# X16-Backplane1.net
KiCad netlist of a schematic drawn in EAGLE
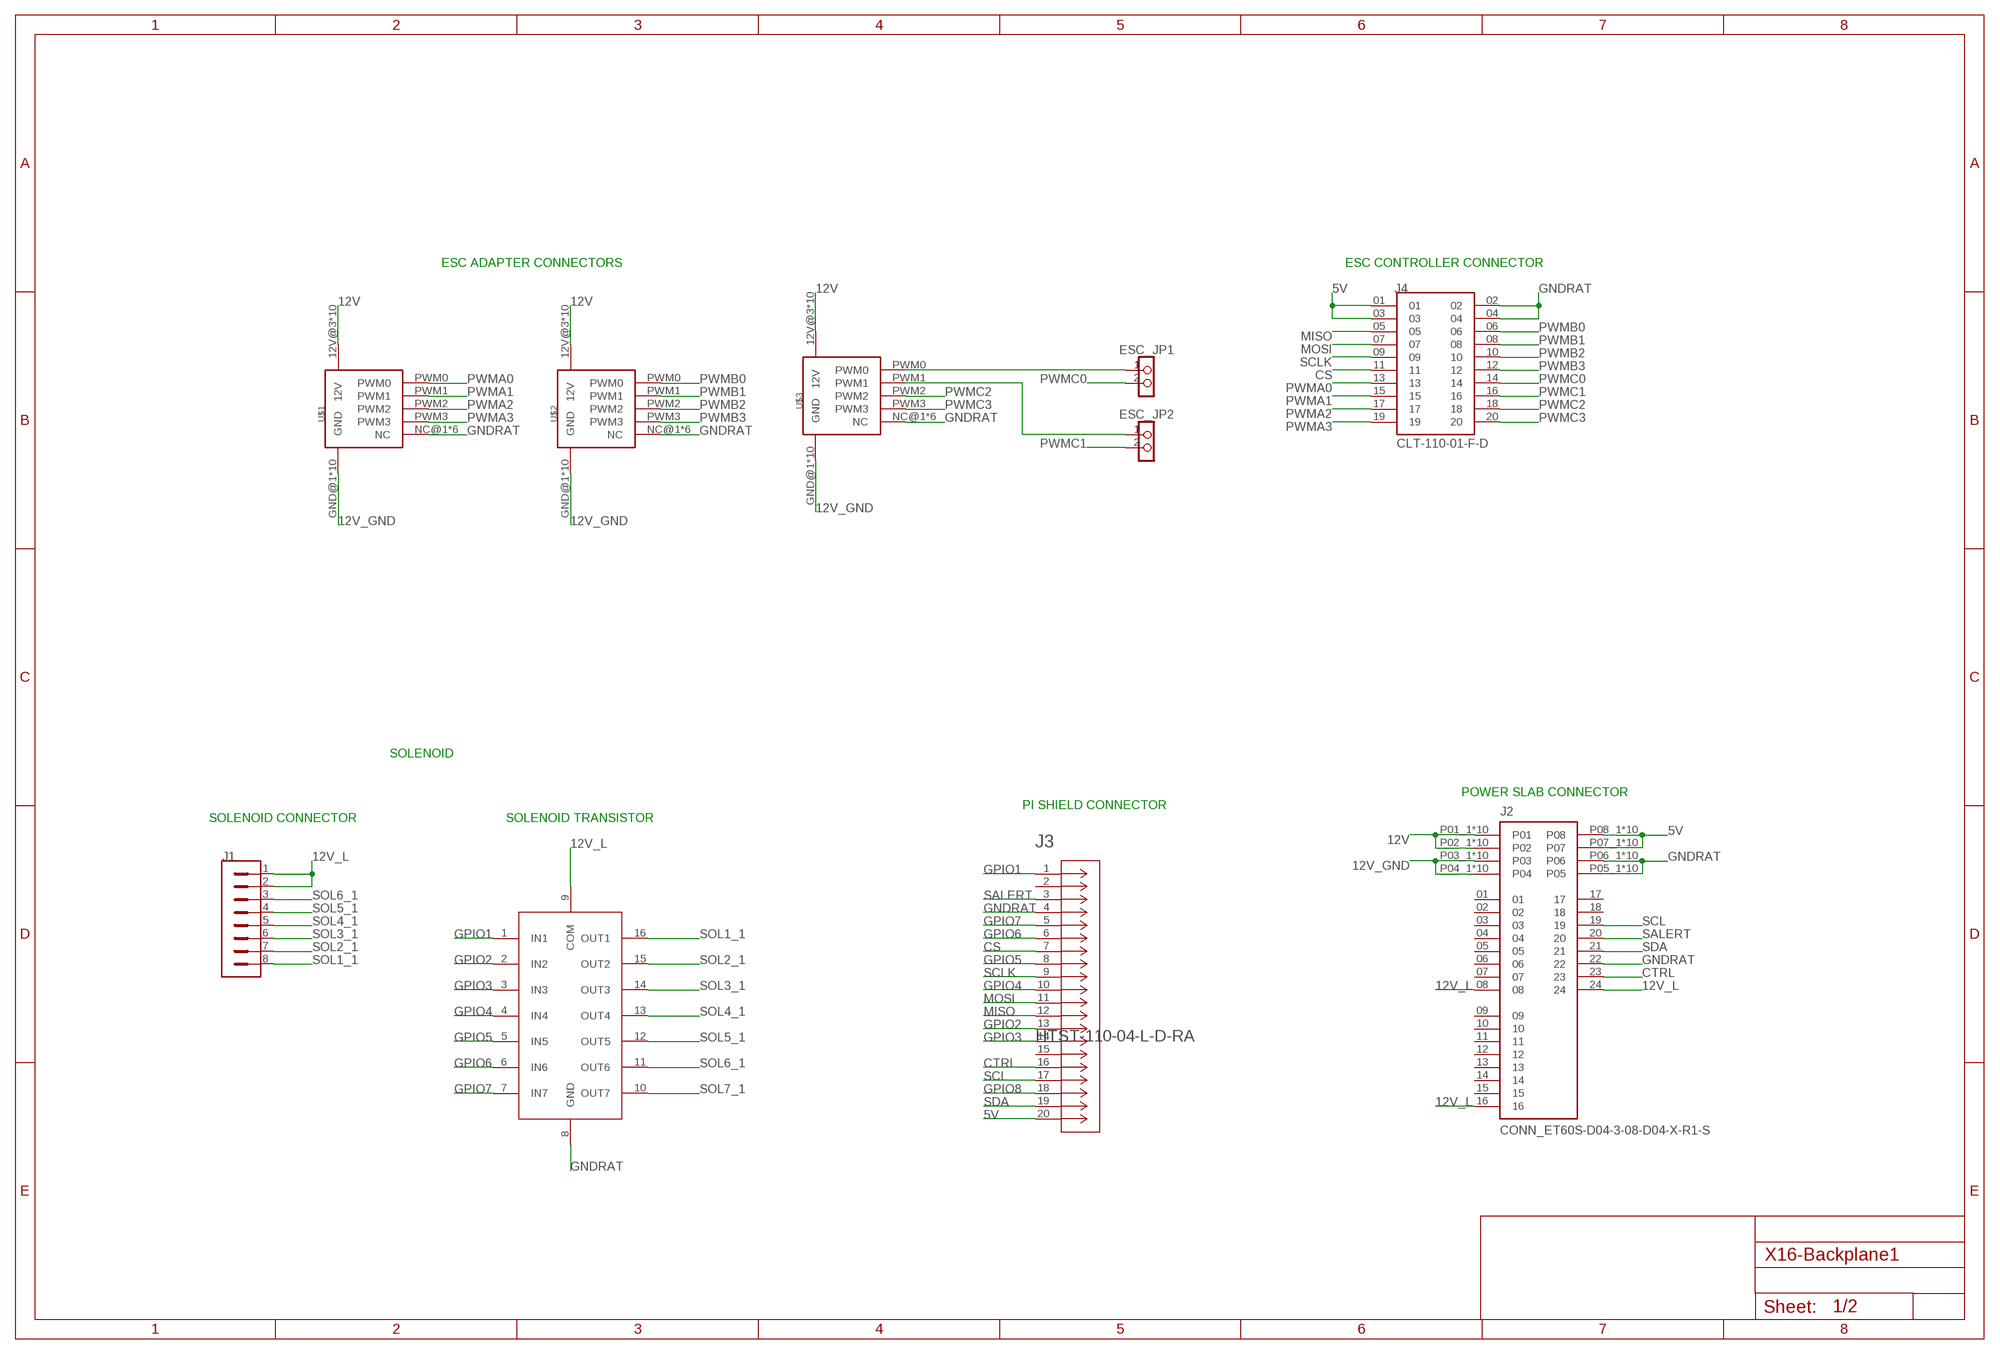
[diagram p0: schematic, sheet 1]
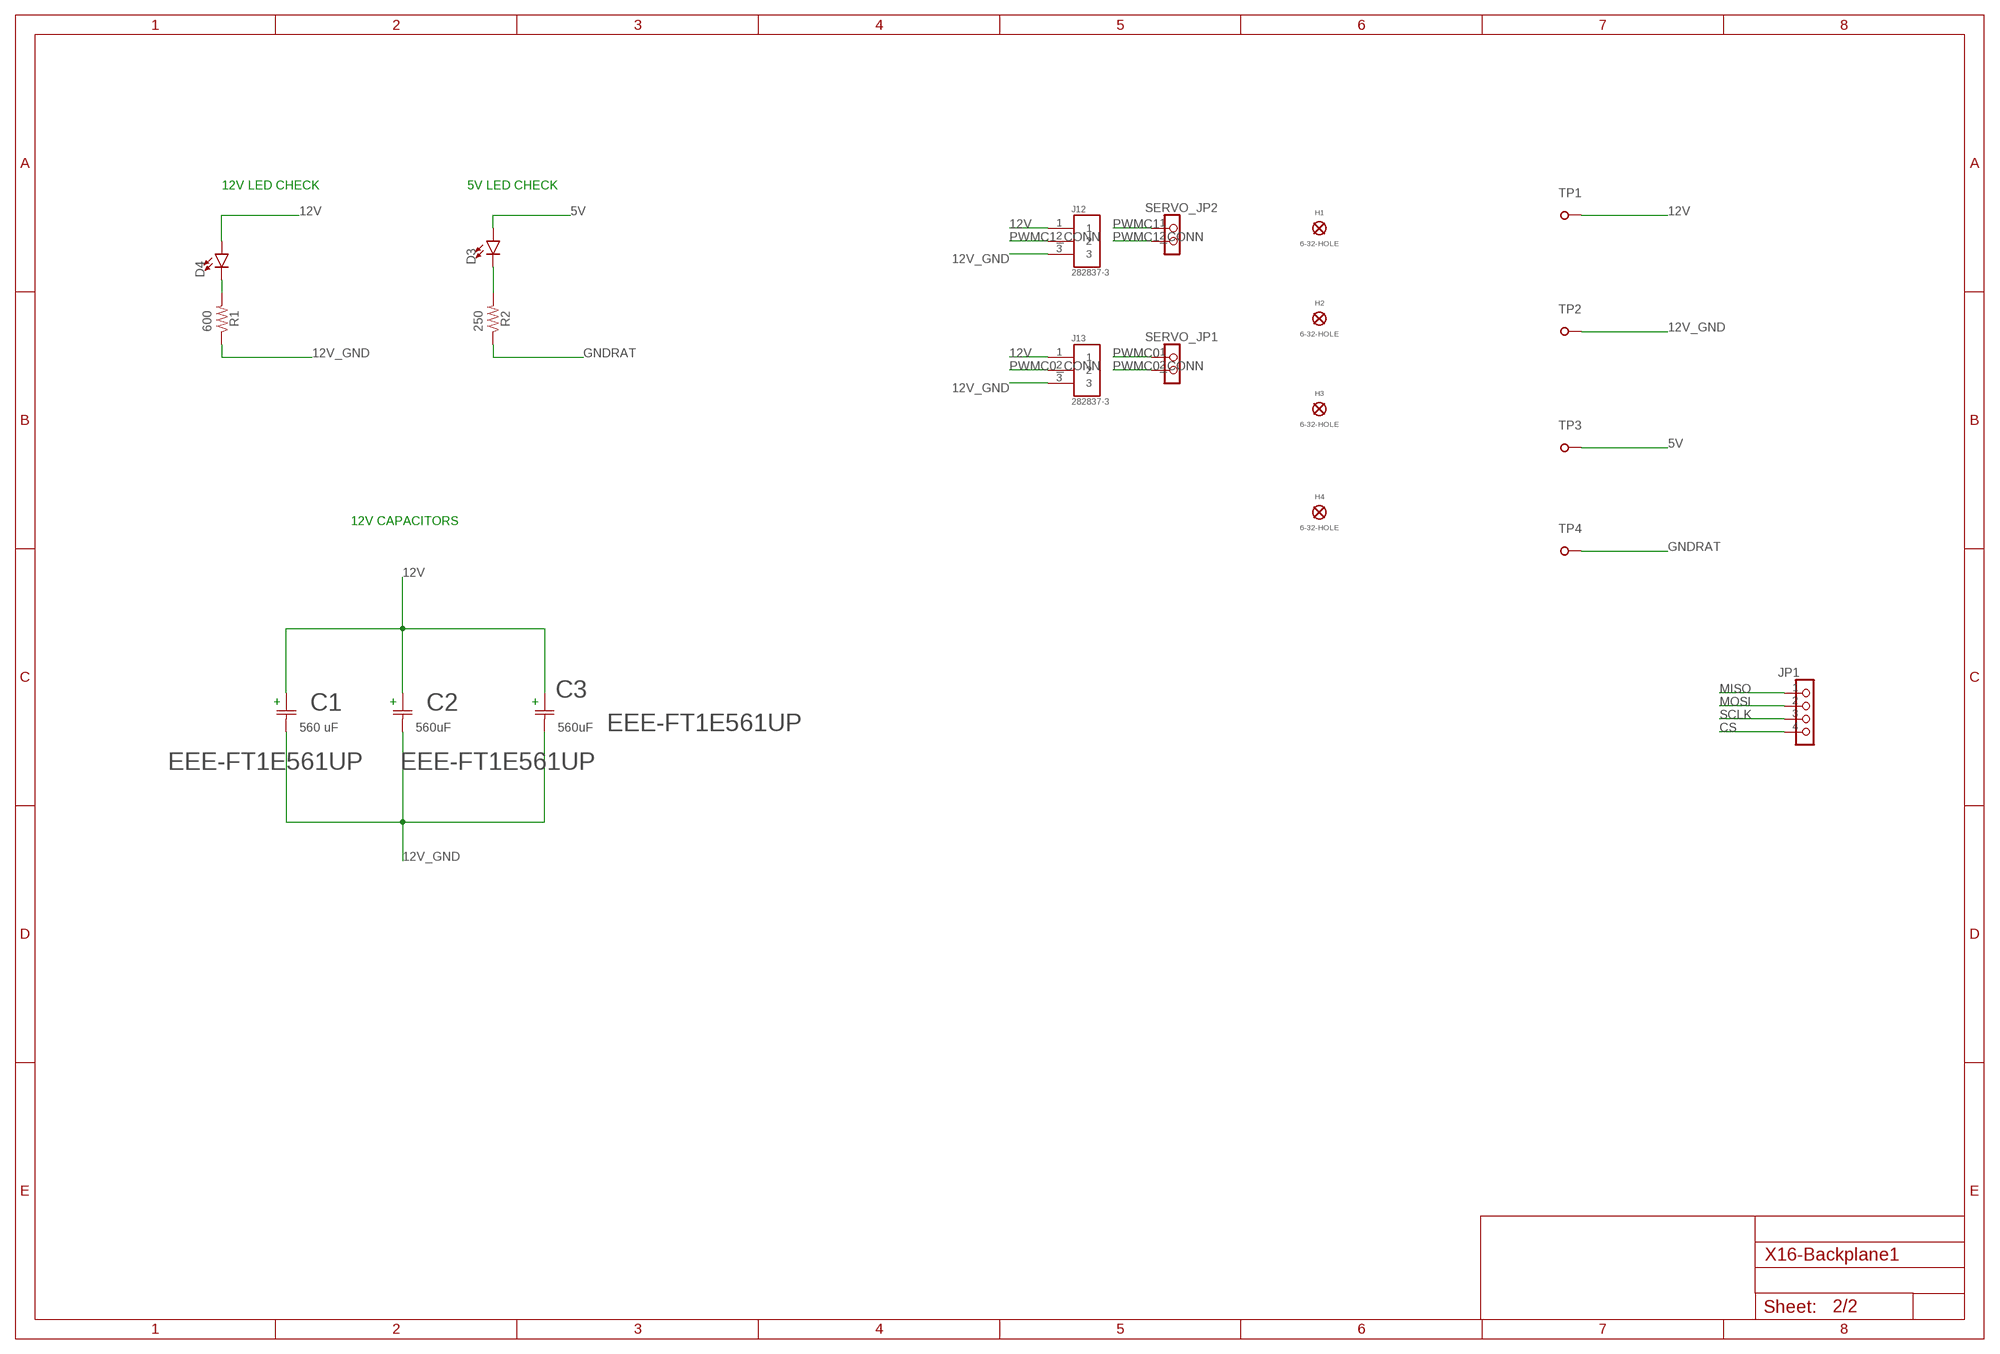
[diagram p1: schematic, sheet 2]

(export (version "E")
  (design (tool "Eeschema 10.0.6"))
  (components
    (comp (ref "ESC_JP1")
      (value "TEST_PIN-1X2")
      (footprint "eagle-import:1X02")
      (libsource (lib "eagle-import") (part "TEST_PIN-1X2"))
    )
    (comp (ref "ESC_JP2")
      (value "TEST_PIN-1X2")
      (footprint "eagle-import:1X02")
      (libsource (lib "eagle-import") (part "TEST_PIN-1X2"))
    )
    (comp (ref "J1")
      (value "CONN_PXC-8-RA-1778683")
      (footprint "eagle-import:PXC-8-RA-1778683")
      (libsource (lib "eagle-import") (part "CONN_PXC-8-RA-1778683"))
    )
    (comp (ref "J2")
      (value "CONN_ET60S-D04-3-08-D04-X-R1-S")
      (footprint "eagle-import:SAMTEC_ET60S-D04-3-08-D04-X-R1-S")
      (fields (field (name "MANUFACTURER") "Samtec"))
      (libsource (lib "eagle-import") (part "CONN_ET60S-D04-3-08-D04-X-R1-S"))
    )
    (comp (ref "J3")
      (value "HTST-110-04-L-D-RA")
      (footprint "eagle-import:CONN_HTST-110-04_05-X-D-RA_SAI")
      (fields (field (name "COPYRIGHT") "Copyright (C) 2023 Ultra Librarian. All rights reserved."))
      (libsource (lib "eagle-import") (part "HTST-110-04-L-D-RA"))
    )
    (comp (ref "J4")
      (value "CLT-110-01-F-D")
      (footprint "eagle-import:SAMTEC_CLT-110-01-F-D")
      (fields (field (name "MANUFACTURER") "SAMTEC"))
      (libsource (lib "eagle-import") (part "CLT-110-01-F-D"))
    )
    (comp (ref "U$1")
      (value "CONN_BACKPLANE_ESC_ADAPTER_NEW")
      (footprint "eagle-import:CONN_BACKPLANE_ESC_ADAPTER")
      (libsource (lib "eagle-import") (part "CONN_BACKPLANE_ESC_ADAPTER_NEW"))
    )
    (comp (ref "U$2")
      (value "CONN_BACKPLANE_ESC_ADAPTER_NEW")
      (footprint "eagle-import:CONN_BACKPLANE_ESC_ADAPTER")
      (libsource (lib "eagle-import") (part "CONN_BACKPLANE_ESC_ADAPTER_NEW"))
    )
    (comp (ref "U$3")
      (value "CONN_BACKPLANE_ESC_ADAPTER_NEW")
      (footprint "eagle-import:CONN_BACKPLANE_ESC_ADAPTER")
      (libsource (lib "eagle-import") (part "CONN_BACKPLANE_ESC_ADAPTER_NEW"))
    )
    (comp (ref "U2")
      (value "TRANS_ULN2003AD")
      (footprint "eagle-import:16-SOIC")
      (fields (field (name "MANUFACTURER") "Diodes Inc."))
      (libsource (lib "eagle-import") (part "TRANS_ULN2003AD"))
    )
    (comp (ref "C1")
      (value "EEE-FT1E561UP")
      (footprint "eagle-import:CAP_FT_F_PAN")
      (fields
        (field (name "C1") "560 uF")
        (field (name "COPYRIGHT") "Copyright (C) 2023 Ultra Librarian. All rights reserved.")
      )
      (libsource (lib "eagle-import") (part "EEE-FT1E561UP"))
    )
    (comp (ref "C2")
      (value "EEE-FT1E561UP")
      (footprint "eagle-import:CAP_FT_F_PAN")
      (fields
        (field (name "C2") "560uF")
        (field (name "COPYRIGHT") "Copyright (C) 2023 Ultra Librarian. All rights reserved.")
      )
      (libsource (lib "eagle-import") (part "EEE-FT1E561UP"))
    )
    (comp (ref "C3")
      (value "EEE-FT1E561UP")
      (footprint "eagle-import:CAP_FT_F_PAN")
      (fields
        (field (name "C3") "560uF")
        (field (name "COPYRIGHT") "Copyright (C) 2023 Ultra Librarian. All rights reserved.")
      )
      (libsource (lib "eagle-import") (part "EEE-FT1E561UP"))
    )
    (comp (ref "D3")
      (value "LEDCHIPLED_0805")
      (footprint "eagle-import:CHIPLED_0805")
      (libsource (lib "eagle-import") (part "LEDCHIPLED_0805"))
    )
    (comp (ref "D4")
      (value "LEDCHIPLED_0805")
      (footprint "eagle-import:CHIPLED_0805")
      (libsource (lib "eagle-import") (part "LEDCHIPLED_0805"))
    )
    (comp (ref "H1")
      (value "6-32-HOLE")
      (footprint "eagle-import:6-32-HOLE")
      (libsource (lib "eagle-import") (part "6-32-HOLE"))
    )
    (comp (ref "H2")
      (value "6-32-HOLE")
      (footprint "eagle-import:6-32-HOLE")
      (libsource (lib "eagle-import") (part "6-32-HOLE"))
    )
    (comp (ref "H3")
      (value "6-32-HOLE")
      (footprint "eagle-import:6-32-HOLE")
      (libsource (lib "eagle-import") (part "6-32-HOLE"))
    )
    (comp (ref "H4")
      (value "6-32-HOLE")
      (footprint "eagle-import:6-32-HOLE")
      (libsource (lib "eagle-import") (part "6-32-HOLE"))
    )
    (comp (ref "J12")
      (value "282837-3")
      (footprint "eagle-import:TE_282837-3")
      (fields (field (name "MANUFACTURER") "TE CONNECTIVITY"))
      (libsource (lib "eagle-import") (part "282837-3"))
    )
    (comp (ref "J13")
      (value "282837-3")
      (footprint "eagle-import:TE_282837-3")
      (fields (field (name "MANUFACTURER") "TE CONNECTIVITY"))
      (libsource (lib "eagle-import") (part "282837-3"))
    )
    (comp (ref "JP1")
      (value "TEST_PIN-1X4")
      (footprint "eagle-import:1X04")
      (libsource (lib "eagle-import") (part "TEST_PIN-1X4"))
    )
    (comp (ref "R1")
      (value "RESISTOR0603")
      (footprint "eagle-import:0603")
      (fields (field (name "PROD_ID") "600"))
      (libsource (lib "eagle-import") (part "RESISTOR0603"))
    )
    (comp (ref "R2")
      (value "RESISTOR0603")
      (footprint "eagle-import:0603")
      (fields (field (name "PROD_ID") "250"))
      (libsource (lib "eagle-import") (part "RESISTOR0603"))
    )
    (comp (ref "SERVO_JP1")
      (value "TEST_PIN-1X2")
      (footprint "eagle-import:1X02")
      (libsource (lib "eagle-import") (part "TEST_PIN-1X2"))
    )
    (comp (ref "SERVO_JP2")
      (value "TEST_PIN-1X2")
      (footprint "eagle-import:1X02")
      (libsource (lib "eagle-import") (part "TEST_PIN-1X2"))
    )
    (comp (ref "TP1")
      (value "TESTPOINT_5.04MM")
      (footprint "eagle-import:TESTPOINT_5.04MM")
      (libsource (lib "eagle-import") (part "TESTPOINT_5.04MM"))
    )
    (comp (ref "TP2")
      (value "TESTPOINT_5.04MM")
      (footprint "eagle-import:TESTPOINT_5.04MM")
      (libsource (lib "eagle-import") (part "TESTPOINT_5.04MM"))
    )
    (comp (ref "TP3")
      (value "TESTPOINT_5.04MM")
      (footprint "eagle-import:TESTPOINT_5.04MM")
      (libsource (lib "eagle-import") (part "TESTPOINT_5.04MM"))
    )
    (comp (ref "TP4")
      (value "TESTPOINT_5.04MM")
      (footprint "eagle-import:TESTPOINT_5.04MM")
      (libsource (lib "eagle-import") (part "TESTPOINT_5.04MM"))
    )
  )
  (nets
    (net (code "1") (name "5V") (class "Default")
      (node (ref "D3") (pin "A") (pinfunction "A_A") (pintype "passive"))
      (node (ref "J2") (pin "P07_1") (pinfunction "P07_P07_1") (pintype "power_in"))
      (node (ref "J2") (pin "P07_10") (pinfunction "P07_P07_10") (pintype "power_in"))
      (node (ref "J2") (pin "P07_2") (pinfunction "P07_P07_2") (pintype "power_in"))
      (node (ref "J2") (pin "P07_3") (pinfunction "P07_P07_3") (pintype "power_in"))
      (node (ref "J2") (pin "P07_4") (pinfunction "P07_P07_4") (pintype "power_in"))
      (node (ref "J2") (pin "P07_5") (pinfunction "P07_P07_5") (pintype "power_in"))
      (node (ref "J2") (pin "P07_6") (pinfunction "P07_P07_6") (pintype "power_in"))
      (node (ref "J2") (pin "P07_7") (pinfunction "P07_P07_7") (pintype "power_in"))
      (node (ref "J2") (pin "P07_8") (pinfunction "P07_P07_8") (pintype "power_in"))
      (node (ref "J2") (pin "P07_9") (pinfunction "P07_P07_9") (pintype "power_in"))
      (node (ref "J2") (pin "P08_1") (pinfunction "P08_P08_1") (pintype "power_in"))
      (node (ref "J2") (pin "P08_10") (pinfunction "P08_P08_10") (pintype "power_in"))
      (node (ref "J2") (pin "P08_2") (pinfunction "P08_P08_2") (pintype "power_in"))
      (node (ref "J2") (pin "P08_3") (pinfunction "P08_P08_3") (pintype "power_in"))
      (node (ref "J2") (pin "P08_4") (pinfunction "P08_P08_4") (pintype "power_in"))
      (node (ref "J2") (pin "P08_5") (pinfunction "P08_P08_5") (pintype "power_in"))
      (node (ref "J2") (pin "P08_6") (pinfunction "P08_P08_6") (pintype "power_in"))
      (node (ref "J2") (pin "P08_7") (pinfunction "P08_P08_7") (pintype "power_in"))
      (node (ref "J2") (pin "P08_8") (pinfunction "P08_P08_8") (pintype "power_in"))
      (node (ref "J2") (pin "P08_9") (pinfunction "P08_P08_9") (pintype "power_in"))
      (node (ref "J3") (pin "20") (pinfunction "20_20") (pintype "passive"))
      (node (ref "J4") (pin "01") (pinfunction "01_01") (pintype "passive"))
      (node (ref "J4") (pin "03") (pinfunction "03_03") (pintype "passive"))
      (node (ref "TP3") (pin "TP") (pinfunction "TP_TP") (pintype "input"))
    )
    (net (code "2") (name "12V") (class "Default")
      (node (ref "C1") (pin "1") (pinfunction "1_1") (pintype "passive"))
      (node (ref "C2") (pin "1") (pinfunction "1_1") (pintype "passive"))
      (node (ref "C3") (pin "1") (pinfunction "1_1") (pintype "passive"))
      (node (ref "D4") (pin "A") (pinfunction "A_A") (pintype "passive"))
      (node (ref "J12") (pin "1") (pinfunction "1_1") (pintype "passive"))
      (node (ref "J13") (pin "1") (pinfunction "1_1") (pintype "passive"))
      (node (ref "J2") (pin "P01_1") (pinfunction "P01_P01_1") (pintype "power_in"))
      (node (ref "J2") (pin "P01_10") (pinfunction "P01_P01_10") (pintype "power_in"))
      (node (ref "J2") (pin "P01_2") (pinfunction "P01_P01_2") (pintype "power_in"))
      (node (ref "J2") (pin "P01_3") (pinfunction "P01_P01_3") (pintype "power_in"))
      (node (ref "J2") (pin "P01_4") (pinfunction "P01_P01_4") (pintype "power_in"))
      (node (ref "J2") (pin "P01_5") (pinfunction "P01_P01_5") (pintype "power_in"))
      (node (ref "J2") (pin "P01_6") (pinfunction "P01_P01_6") (pintype "power_in"))
      (node (ref "J2") (pin "P01_7") (pinfunction "P01_P01_7") (pintype "power_in"))
      (node (ref "J2") (pin "P01_8") (pinfunction "P01_P01_8") (pintype "power_in"))
      (node (ref "J2") (pin "P01_9") (pinfunction "P01_P01_9") (pintype "power_in"))
      (node (ref "J2") (pin "P02_1") (pinfunction "P02_P02_1") (pintype "power_in"))
      (node (ref "J2") (pin "P02_10") (pinfunction "P02_P02_10") (pintype "power_in"))
      (node (ref "J2") (pin "P02_2") (pinfunction "P02_P02_2") (pintype "power_in"))
      (node (ref "J2") (pin "P02_3") (pinfunction "P02_P02_3") (pintype "power_in"))
      (node (ref "J2") (pin "P02_4") (pinfunction "P02_P02_4") (pintype "power_in"))
      (node (ref "J2") (pin "P02_5") (pinfunction "P02_P02_5") (pintype "power_in"))
      (node (ref "J2") (pin "P02_6") (pinfunction "P02_P02_6") (pintype "power_in"))
      (node (ref "J2") (pin "P02_7") (pinfunction "P02_P02_7") (pintype "power_in"))
      (node (ref "J2") (pin "P02_8") (pinfunction "P02_P02_8") (pintype "power_in"))
      (node (ref "J2") (pin "P02_9") (pinfunction "P02_P02_9") (pintype "power_in"))
      (node (ref "TP1") (pin "TP") (pinfunction "TP_TP") (pintype "input"))
      (node (ref "U$1") (pin "12V@10") (pinfunction "12V_12V@10") (pintype "bidirectional"))
      (node (ref "U$1") (pin "12V@11") (pinfunction "12V_12V@11") (pintype "bidirectional"))
      (node (ref "U$1") (pin "12V@12") (pinfunction "12V_12V@12") (pintype "bidirectional"))
      (node (ref "U$1") (pin "12V@3") (pinfunction "12V_12V@3") (pintype "bidirectional"))
      (node (ref "U$1") (pin "12V@4") (pinfunction "12V_12V@4") (pintype "bidirectional"))
      (node (ref "U$1") (pin "12V@5") (pinfunction "12V_12V@5") (pintype "bidirectional"))
      (node (ref "U$1") (pin "12V@6") (pinfunction "12V_12V@6") (pintype "bidirectional"))
      (node (ref "U$1") (pin "12V@7") (pinfunction "12V_12V@7") (pintype "bidirectional"))
      (node (ref "U$1") (pin "12V@8") (pinfunction "12V_12V@8") (pintype "bidirectional"))
      (node (ref "U$1") (pin "12V@9") (pinfunction "12V_12V@9") (pintype "bidirectional"))
      (node (ref "U$2") (pin "12V@10") (pinfunction "12V_12V@10") (pintype "bidirectional"))
      (node (ref "U$2") (pin "12V@11") (pinfunction "12V_12V@11") (pintype "bidirectional"))
      (node (ref "U$2") (pin "12V@12") (pinfunction "12V_12V@12") (pintype "bidirectional"))
      (node (ref "U$2") (pin "12V@3") (pinfunction "12V_12V@3") (pintype "bidirectional"))
      (node (ref "U$2") (pin "12V@4") (pinfunction "12V_12V@4") (pintype "bidirectional"))
      (node (ref "U$2") (pin "12V@5") (pinfunction "12V_12V@5") (pintype "bidirectional"))
      (node (ref "U$2") (pin "12V@6") (pinfunction "12V_12V@6") (pintype "bidirectional"))
      (node (ref "U$2") (pin "12V@7") (pinfunction "12V_12V@7") (pintype "bidirectional"))
      (node (ref "U$2") (pin "12V@8") (pinfunction "12V_12V@8") (pintype "bidirectional"))
      (node (ref "U$2") (pin "12V@9") (pinfunction "12V_12V@9") (pintype "bidirectional"))
      (node (ref "U$3") (pin "12V@10") (pinfunction "12V_12V@10") (pintype "bidirectional"))
      (node (ref "U$3") (pin "12V@11") (pinfunction "12V_12V@11") (pintype "bidirectional"))
      (node (ref "U$3") (pin "12V@12") (pinfunction "12V_12V@12") (pintype "bidirectional"))
      (node (ref "U$3") (pin "12V@3") (pinfunction "12V_12V@3") (pintype "bidirectional"))
      (node (ref "U$3") (pin "12V@4") (pinfunction "12V_12V@4") (pintype "bidirectional"))
      (node (ref "U$3") (pin "12V@5") (pinfunction "12V_12V@5") (pintype "bidirectional"))
      (node (ref "U$3") (pin "12V@6") (pinfunction "12V_12V@6") (pintype "bidirectional"))
      (node (ref "U$3") (pin "12V@7") (pinfunction "12V_12V@7") (pintype "bidirectional"))
      (node (ref "U$3") (pin "12V@8") (pinfunction "12V_12V@8") (pintype "bidirectional"))
      (node (ref "U$3") (pin "12V@9") (pinfunction "12V_12V@9") (pintype "bidirectional"))
    )
    (net (code "3") (name "12V_GND") (class "Default")
      (node (ref "C1") (pin "2") (pinfunction "2_2") (pintype "passive"))
      (node (ref "C2") (pin "2") (pinfunction "2_2") (pintype "passive"))
      (node (ref "C3") (pin "2") (pinfunction "2_2") (pintype "passive"))
      (node (ref "J12") (pin "3") (pinfunction "3_3") (pintype "passive"))
      (node (ref "J13") (pin "3") (pinfunction "3_3") (pintype "passive"))
      (node (ref "J2") (pin "P03_1") (pinfunction "P03_P03_1") (pintype "power_in"))
      (node (ref "J2") (pin "P03_10") (pinfunction "P03_P03_10") (pintype "power_in"))
      (node (ref "J2") (pin "P03_2") (pinfunction "P03_P03_2") (pintype "power_in"))
      (node (ref "J2") (pin "P03_3") (pinfunction "P03_P03_3") (pintype "power_in"))
      (node (ref "J2") (pin "P03_4") (pinfunction "P03_P03_4") (pintype "power_in"))
      (node (ref "J2") (pin "P03_5") (pinfunction "P03_P03_5") (pintype "power_in"))
      (node (ref "J2") (pin "P03_6") (pinfunction "P03_P03_6") (pintype "power_in"))
      (node (ref "J2") (pin "P03_7") (pinfunction "P03_P03_7") (pintype "power_in"))
      (node (ref "J2") (pin "P03_8") (pinfunction "P03_P03_8") (pintype "power_in"))
      (node (ref "J2") (pin "P03_9") (pinfunction "P03_P03_9") (pintype "power_in"))
      (node (ref "J2") (pin "P04_1") (pinfunction "P04_P04_1") (pintype "power_in"))
      (node (ref "J2") (pin "P04_10") (pinfunction "P04_P04_10") (pintype "power_in"))
      (node (ref "J2") (pin "P04_2") (pinfunction "P04_P04_2") (pintype "power_in"))
      (node (ref "J2") (pin "P04_3") (pinfunction "P04_P04_3") (pintype "power_in"))
      (node (ref "J2") (pin "P04_4") (pinfunction "P04_P04_4") (pintype "power_in"))
      (node (ref "J2") (pin "P04_5") (pinfunction "P04_P04_5") (pintype "power_in"))
      (node (ref "J2") (pin "P04_6") (pinfunction "P04_P04_6") (pintype "power_in"))
      (node (ref "J2") (pin "P04_7") (pinfunction "P04_P04_7") (pintype "power_in"))
      (node (ref "J2") (pin "P04_8") (pinfunction "P04_P04_8") (pintype "power_in"))
      (node (ref "J2") (pin "P04_9") (pinfunction "P04_P04_9") (pintype "power_in"))
      (node (ref "R1") (pin "1") (pinfunction "1_1") (pintype "passive"))
      (node (ref "TP2") (pin "TP") (pinfunction "TP_TP") (pintype "input"))
      (node (ref "U$1") (pin "GND@1") (pinfunction "GND_GND@1") (pintype "bidirectional"))
      (node (ref "U$1") (pin "GND@10") (pinfunction "GND_GND@10") (pintype "bidirectional"))
      (node (ref "U$1") (pin "GND@2") (pinfunction "GND_GND@2") (pintype "bidirectional"))
      (node (ref "U$1") (pin "GND@3") (pinfunction "GND_GND@3") (pintype "bidirectional"))
      (node (ref "U$1") (pin "GND@4") (pinfunction "GND_GND@4") (pintype "bidirectional"))
      (node (ref "U$1") (pin "GND@5") (pinfunction "GND_GND@5") (pintype "bidirectional"))
      (node (ref "U$1") (pin "GND@6") (pinfunction "GND_GND@6") (pintype "bidirectional"))
      (node (ref "U$1") (pin "GND@7") (pinfunction "GND_GND@7") (pintype "bidirectional"))
      (node (ref "U$1") (pin "GND@8") (pinfunction "GND_GND@8") (pintype "bidirectional"))
      (node (ref "U$1") (pin "GND@9") (pinfunction "GND_GND@9") (pintype "bidirectional"))
      (node (ref "U$2") (pin "GND@1") (pinfunction "GND_GND@1") (pintype "bidirectional"))
      (node (ref "U$2") (pin "GND@10") (pinfunction "GND_GND@10") (pintype "bidirectional"))
      (node (ref "U$2") (pin "GND@2") (pinfunction "GND_GND@2") (pintype "bidirectional"))
      (node (ref "U$2") (pin "GND@3") (pinfunction "GND_GND@3") (pintype "bidirectional"))
      (node (ref "U$2") (pin "GND@4") (pinfunction "GND_GND@4") (pintype "bidirectional"))
      (node (ref "U$2") (pin "GND@5") (pinfunction "GND_GND@5") (pintype "bidirectional"))
      (node (ref "U$2") (pin "GND@6") (pinfunction "GND_GND@6") (pintype "bidirectional"))
      (node (ref "U$2") (pin "GND@7") (pinfunction "GND_GND@7") (pintype "bidirectional"))
      (node (ref "U$2") (pin "GND@8") (pinfunction "GND_GND@8") (pintype "bidirectional"))
      (node (ref "U$2") (pin "GND@9") (pinfunction "GND_GND@9") (pintype "bidirectional"))
      (node (ref "U$3") (pin "GND@1") (pinfunction "GND_GND@1") (pintype "bidirectional"))
      (node (ref "U$3") (pin "GND@10") (pinfunction "GND_GND@10") (pintype "bidirectional"))
      (node (ref "U$3") (pin "GND@2") (pinfunction "GND_GND@2") (pintype "bidirectional"))
      (node (ref "U$3") (pin "GND@3") (pinfunction "GND_GND@3") (pintype "bidirectional"))
      (node (ref "U$3") (pin "GND@4") (pinfunction "GND_GND@4") (pintype "bidirectional"))
      (node (ref "U$3") (pin "GND@5") (pinfunction "GND_GND@5") (pintype "bidirectional"))
      (node (ref "U$3") (pin "GND@6") (pinfunction "GND_GND@6") (pintype "bidirectional"))
      (node (ref "U$3") (pin "GND@7") (pinfunction "GND_GND@7") (pintype "bidirectional"))
      (node (ref "U$3") (pin "GND@8") (pinfunction "GND_GND@8") (pintype "bidirectional"))
      (node (ref "U$3") (pin "GND@9") (pinfunction "GND_GND@9") (pintype "bidirectional"))
    )
    (net (code "4") (name "12V_L") (class "Default")
      (node (ref "J1") (pin "1") (pinfunction "1_1") (pintype "passive"))
      (node (ref "J1") (pin "2") (pinfunction "2_2") (pintype "passive"))
      (node (ref "J2") (pin "08") (pinfunction "08_08") (pintype "passive"))
      (node (ref "J2") (pin "16") (pinfunction "16_16") (pintype "passive"))
      (node (ref "J2") (pin "24") (pinfunction "24_24") (pintype "passive"))
      (node (ref "U2") (pin "9") (pinfunction "COM_9") (pintype "bidirectional"))
    )
    (net (code "5") (name "CS") (class "Default")
      (node (ref "J3") (pin "7") (pinfunction "7_7") (pintype "passive"))
      (node (ref "J4") (pin "11") (pinfunction "11_11") (pintype "passive"))
      (node (ref "JP1") (pin "4") (pinfunction "4_4") (pintype "passive"))
    )
    (net (code "6") (name "CTRL") (class "Default")
      (node (ref "J2") (pin "23") (pinfunction "23_23") (pintype "passive"))
      (node (ref "J3") (pin "16") (pinfunction "16_16") (pintype "passive"))
    )
    (net (code "7") (name "GNDRAT") (class "Default")
      (node (ref "J2") (pin "22") (pinfunction "22_22") (pintype "passive"))
      (node (ref "J2") (pin "P05_1") (pinfunction "P05_P05_1") (pintype "power_in"))
      (node (ref "J2") (pin "P05_10") (pinfunction "P05_P05_10") (pintype "power_in"))
      (node (ref "J2") (pin "P05_2") (pinfunction "P05_P05_2") (pintype "power_in"))
      (node (ref "J2") (pin "P05_3") (pinfunction "P05_P05_3") (pintype "power_in"))
      (node (ref "J2") (pin "P05_4") (pinfunction "P05_P05_4") (pintype "power_in"))
      (node (ref "J2") (pin "P05_5") (pinfunction "P05_P05_5") (pintype "power_in"))
      (node (ref "J2") (pin "P05_6") (pinfunction "P05_P05_6") (pintype "power_in"))
      (node (ref "J2") (pin "P05_7") (pinfunction "P05_P05_7") (pintype "power_in"))
      (node (ref "J2") (pin "P05_8") (pinfunction "P05_P05_8") (pintype "power_in"))
      (node (ref "J2") (pin "P05_9") (pinfunction "P05_P05_9") (pintype "power_in"))
      (node (ref "J2") (pin "P06_1") (pinfunction "P06_P06_1") (pintype "power_in"))
      (node (ref "J2") (pin "P06_10") (pinfunction "P06_P06_10") (pintype "power_in"))
      (node (ref "J2") (pin "P06_2") (pinfunction "P06_P06_2") (pintype "power_in"))
      (node (ref "J2") (pin "P06_3") (pinfunction "P06_P06_3") (pintype "power_in"))
      (node (ref "J2") (pin "P06_4") (pinfunction "P06_P06_4") (pintype "power_in"))
      (node (ref "J2") (pin "P06_5") (pinfunction "P06_P06_5") (pintype "power_in"))
      (node (ref "J2") (pin "P06_6") (pinfunction "P06_P06_6") (pintype "power_in"))
      (node (ref "J2") (pin "P06_7") (pinfunction "P06_P06_7") (pintype "power_in"))
      (node (ref "J2") (pin "P06_8") (pinfunction "P06_P06_8") (pintype "power_in"))
      (node (ref "J2") (pin "P06_9") (pinfunction "P06_P06_9") (pintype "power_in"))
      (node (ref "J3") (pin "4") (pinfunction "4_4") (pintype "passive"))
      (node (ref "J4") (pin "02") (pinfunction "02_02") (pintype "passive"))
      (node (ref "J4") (pin "04") (pinfunction "04_04") (pintype "passive"))
      (node (ref "R2") (pin "1") (pinfunction "1_1") (pintype "passive"))
      (node (ref "TP4") (pin "TP") (pinfunction "TP_TP") (pintype "input"))
      (node (ref "U$1") (pin "NC@1") (pinfunction "NC_NC@1") (pintype "bidirectional"))
      (node (ref "U$1") (pin "NC@2") (pinfunction "NC_NC@2") (pintype "bidirectional"))
      (node (ref "U$1") (pin "NC@3") (pinfunction "NC_NC@3") (pintype "bidirectional"))
      (node (ref "U$1") (pin "NC@4") (pinfunction "NC_NC@4") (pintype "bidirectional"))
      (node (ref "U$1") (pin "NC@5") (pinfunction "NC_NC@5") (pintype "bidirectional"))
      (node (ref "U$1") (pin "NC@6") (pinfunction "NC_NC@6") (pintype "bidirectional"))
      (node (ref "U$2") (pin "NC@1") (pinfunction "NC_NC@1") (pintype "bidirectional"))
      (node (ref "U$2") (pin "NC@2") (pinfunction "NC_NC@2") (pintype "bidirectional"))
      (node (ref "U$2") (pin "NC@3") (pinfunction "NC_NC@3") (pintype "bidirectional"))
      (node (ref "U$2") (pin "NC@4") (pinfunction "NC_NC@4") (pintype "bidirectional"))
      (node (ref "U$2") (pin "NC@5") (pinfunction "NC_NC@5") (pintype "bidirectional"))
      (node (ref "U$2") (pin "NC@6") (pinfunction "NC_NC@6") (pintype "bidirectional"))
      (node (ref "U$3") (pin "NC@1") (pinfunction "NC_NC@1") (pintype "bidirectional"))
      (node (ref "U$3") (pin "NC@2") (pinfunction "NC_NC@2") (pintype "bidirectional"))
      (node (ref "U$3") (pin "NC@3") (pinfunction "NC_NC@3") (pintype "bidirectional"))
      (node (ref "U$3") (pin "NC@4") (pinfunction "NC_NC@4") (pintype "bidirectional"))
      (node (ref "U$3") (pin "NC@5") (pinfunction "NC_NC@5") (pintype "bidirectional"))
      (node (ref "U$3") (pin "NC@6") (pinfunction "NC_NC@6") (pintype "bidirectional"))
      (node (ref "U2") (pin "8") (pinfunction "GND_8") (pintype "bidirectional"))
    )
    (net (code "8") (name "GPIO1") (class "Default")
      (node (ref "J3") (pin "1") (pinfunction "1_1") (pintype "passive"))
      (node (ref "U2") (pin "1") (pinfunction "IN1_1") (pintype "bidirectional"))
    )
    (net (code "9") (name "GPIO2") (class "Default")
      (node (ref "J3") (pin "13") (pinfunction "13_13") (pintype "passive"))
      (node (ref "U2") (pin "2") (pinfunction "IN2_2") (pintype "bidirectional"))
    )
    (net (code "10") (name "GPIO3") (class "Default")
      (node (ref "J3") (pin "14") (pinfunction "14_14") (pintype "passive"))
      (node (ref "U2") (pin "3") (pinfunction "IN3_3") (pintype "bidirectional"))
    )
    (net (code "11") (name "GPIO4") (class "Default")
      (node (ref "J3") (pin "10") (pinfunction "10_10") (pintype "passive"))
      (node (ref "U2") (pin "4") (pinfunction "IN4_4") (pintype "bidirectional"))
    )
    (net (code "12") (name "GPIO5") (class "Default")
      (node (ref "J3") (pin "8") (pinfunction "8_8") (pintype "passive"))
      (node (ref "U2") (pin "5") (pinfunction "IN5_5") (pintype "bidirectional"))
    )
    (net (code "13") (name "GPIO6") (class "Default")
      (node (ref "J3") (pin "6") (pinfunction "6_6") (pintype "passive"))
      (node (ref "U2") (pin "6") (pinfunction "IN6_6") (pintype "bidirectional"))
    )
    (net (code "14") (name "GPIO7") (class "Default")
      (node (ref "J3") (pin "5") (pinfunction "5_5") (pintype "passive"))
      (node (ref "U2") (pin "7") (pinfunction "IN7_7") (pintype "bidirectional"))
    )
    (net (code "15") (name "GPIO8") (class "Default")
      (node (ref "J3") (pin "18") (pinfunction "18_18") (pintype "passive"))
    )
    (net (code "16") (name "MISO") (class "Default")
      (node (ref "J3") (pin "12") (pinfunction "12_12") (pintype "passive"))
      (node (ref "J4") (pin "05") (pinfunction "05_05") (pintype "passive"))
      (node (ref "JP1") (pin "1") (pinfunction "1_1") (pintype "passive"))
    )
    (net (code "17") (name "MOSI") (class "Default")
      (node (ref "J3") (pin "11") (pinfunction "11_11") (pintype "passive"))
      (node (ref "J4") (pin "07") (pinfunction "07_07") (pintype "passive"))
      (node (ref "JP1") (pin "2") (pinfunction "2_2") (pintype "passive"))
    )
    (net (code "18") (name "Net-(D3-PadC)") (class "Default")
      (node (ref "D3") (pin "C") (pinfunction "C_C") (pintype "passive"))
      (node (ref "R2") (pin "2") (pinfunction "2_2") (pintype "passive"))
    )
    (net (code "19") (name "Net-(D4-PadC)") (class "Default")
      (node (ref "D4") (pin "C") (pinfunction "C_C") (pintype "passive"))
      (node (ref "R1") (pin "2") (pinfunction "2_2") (pintype "passive"))
    )
    (net (code "20") (name "Net-(ESC_JP1-Pad1)") (class "Default")
      (node (ref "ESC_JP1") (pin "1") (pinfunction "1_1") (pintype "passive"))
      (node (ref "U$3") (pin "PWM0") (pinfunction "PWM0_PWM0") (pintype "bidirectional"))
    )
    (net (code "21") (name "Net-(ESC_JP2-Pad1)") (class "Default")
      (node (ref "ESC_JP2") (pin "1") (pinfunction "1_1") (pintype "passive"))
      (node (ref "U$3") (pin "PWM1") (pinfunction "PWM1_PWM1") (pintype "bidirectional"))
    )
    (net (code "22") (name "PWMA0") (class "Default")
      (node (ref "J4") (pin "13") (pinfunction "13_13") (pintype "passive"))
      (node (ref "U$1") (pin "PWM0") (pinfunction "PWM0_PWM0") (pintype "bidirectional"))
    )
    (net (code "23") (name "PWMA1") (class "Default")
      (node (ref "J4") (pin "15") (pinfunction "15_15") (pintype "passive"))
      (node (ref "U$1") (pin "PWM1") (pinfunction "PWM1_PWM1") (pintype "bidirectional"))
    )
    (net (code "24") (name "PWMA2") (class "Default")
      (node (ref "J4") (pin "17") (pinfunction "17_17") (pintype "passive"))
      (node (ref "U$1") (pin "PWM2") (pinfunction "PWM2_PWM2") (pintype "bidirectional"))
    )
    (net (code "25") (name "PWMA3") (class "Default")
      (node (ref "J4") (pin "19") (pinfunction "19_19") (pintype "passive"))
      (node (ref "U$1") (pin "PWM3") (pinfunction "PWM3_PWM3") (pintype "bidirectional"))
    )
    (net (code "26") (name "PWMB0") (class "Default")
      (node (ref "J4") (pin "06") (pinfunction "06_06") (pintype "passive"))
      (node (ref "U$2") (pin "PWM0") (pinfunction "PWM0_PWM0") (pintype "bidirectional"))
    )
    (net (code "27") (name "PWMB1") (class "Default")
      (node (ref "J4") (pin "08") (pinfunction "08_08") (pintype "passive"))
      (node (ref "U$2") (pin "PWM1") (pinfunction "PWM1_PWM1") (pintype "bidirectional"))
    )
    (net (code "28") (name "PWMB2") (class "Default")
      (node (ref "J4") (pin "10") (pinfunction "10_10") (pintype "passive"))
      (node (ref "U$2") (pin "PWM2") (pinfunction "PWM2_PWM2") (pintype "bidirectional"))
    )
    (net (code "29") (name "PWMB3") (class "Default")
      (node (ref "J4") (pin "12") (pinfunction "12_12") (pintype "passive"))
      (node (ref "U$2") (pin "PWM3") (pinfunction "PWM3_PWM3") (pintype "bidirectional"))
    )
    (net (code "30") (name "PWMC0") (class "Default")
      (node (ref "ESC_JP1") (pin "2") (pinfunction "2_2") (pintype "passive"))
      (node (ref "J4") (pin "14") (pinfunction "14_14") (pintype "passive"))
      (node (ref "SERVO_JP1") (pin "1") (pinfunction "1_1") (pintype "passive"))
    )
    (net (code "31") (name "PWMC0_CONN") (class "Default")
      (node (ref "J13") (pin "2") (pinfunction "2_2") (pintype "passive"))
      (node (ref "SERVO_JP1") (pin "2") (pinfunction "2_2") (pintype "passive"))
    )
    (net (code "32") (name "PWMC1") (class "Default")
      (node (ref "ESC_JP2") (pin "2") (pinfunction "2_2") (pintype "passive"))
      (node (ref "J4") (pin "16") (pinfunction "16_16") (pintype "passive"))
      (node (ref "SERVO_JP2") (pin "1") (pinfunction "1_1") (pintype "passive"))
    )
    (net (code "33") (name "PWMC1_CONN") (class "Default")
      (node (ref "J12") (pin "2") (pinfunction "2_2") (pintype "passive"))
      (node (ref "SERVO_JP2") (pin "2") (pinfunction "2_2") (pintype "passive"))
    )
    (net (code "34") (name "PWMC2") (class "Default")
      (node (ref "J4") (pin "18") (pinfunction "18_18") (pintype "passive"))
      (node (ref "U$3") (pin "PWM2") (pinfunction "PWM2_PWM2") (pintype "bidirectional"))
    )
    (net (code "35") (name "PWMC3") (class "Default")
      (node (ref "J4") (pin "20") (pinfunction "20_20") (pintype "passive"))
      (node (ref "U$3") (pin "PWM3") (pinfunction "PWM3_PWM3") (pintype "bidirectional"))
    )
    (net (code "36") (name "SALERT") (class "Default")
      (node (ref "J2") (pin "20") (pinfunction "20_20") (pintype "passive"))
      (node (ref "J3") (pin "3") (pinfunction "3_3") (pintype "passive"))
    )
    (net (code "37") (name "SCL") (class "Default")
      (node (ref "J2") (pin "19") (pinfunction "19_19") (pintype "passive"))
      (node (ref "J3") (pin "17") (pinfunction "17_17") (pintype "passive"))
    )
    (net (code "38") (name "SCLK") (class "Default")
      (node (ref "J3") (pin "9") (pinfunction "9_9") (pintype "passive"))
      (node (ref "J4") (pin "09") (pinfunction "09_09") (pintype "passive"))
      (node (ref "JP1") (pin "3") (pinfunction "3_3") (pintype "passive"))
    )
    (net (code "39") (name "SDA") (class "Default")
      (node (ref "J2") (pin "21") (pinfunction "21_21") (pintype "passive"))
      (node (ref "J3") (pin "19") (pinfunction "19_19") (pintype "passive"))
    )
    (net (code "40") (name "SOL1_1") (class "Default")
      (node (ref "J1") (pin "8") (pinfunction "8_8") (pintype "passive"))
      (node (ref "U2") (pin "16") (pinfunction "OUT1_16") (pintype "bidirectional"))
    )
    (net (code "41") (name "SOL2_1") (class "Default")
      (node (ref "J1") (pin "7") (pinfunction "7_7") (pintype "passive"))
      (node (ref "U2") (pin "15") (pinfunction "OUT2_15") (pintype "bidirectional"))
    )
    (net (code "42") (name "SOL3_1") (class "Default")
      (node (ref "J1") (pin "6") (pinfunction "6_6") (pintype "passive"))
      (node (ref "U2") (pin "14") (pinfunction "OUT3_14") (pintype "bidirectional"))
    )
    (net (code "43") (name "SOL4_1") (class "Default")
      (node (ref "J1") (pin "5") (pinfunction "5_5") (pintype "passive"))
      (node (ref "U2") (pin "13") (pinfunction "OUT4_13") (pintype "bidirectional"))
    )
    (net (code "44") (name "SOL5_1") (class "Default")
      (node (ref "J1") (pin "4") (pinfunction "4_4") (pintype "passive"))
      (node (ref "U2") (pin "12") (pinfunction "OUT5_12") (pintype "bidirectional"))
    )
    (net (code "45") (name "SOL6_1") (class "Default")
      (node (ref "J1") (pin "3") (pinfunction "3_3") (pintype "passive"))
      (node (ref "U2") (pin "11") (pinfunction "OUT6_11") (pintype "bidirectional"))
    )
    (net (code "46") (name "SOL7_1") (class "Default")
      (node (ref "U2") (pin "10") (pinfunction "OUT7_10") (pintype "bidirectional"))
    )
    (net (code "47") (name "unconnected-(J2-Pad01)") (class "Default")
      (node (ref "J2") (pin "01") (pinfunction "01_01") (pintype "passive"))
    )
    (net (code "48") (name "unconnected-(J2-Pad02)") (class "Default")
      (node (ref "J2") (pin "02") (pinfunction "02_02") (pintype "passive"))
    )
    (net (code "49") (name "unconnected-(J2-Pad03)") (class "Default")
      (node (ref "J2") (pin "03") (pinfunction "03_03") (pintype "passive"))
    )
    (net (code "50") (name "unconnected-(J2-Pad04)") (class "Default")
      (node (ref "J2") (pin "04") (pinfunction "04_04") (pintype "passive"))
    )
    (net (code "51") (name "unconnected-(J2-Pad05)") (class "Default")
      (node (ref "J2") (pin "05") (pinfunction "05_05") (pintype "passive"))
    )
    (net (code "52") (name "unconnected-(J2-Pad06)") (class "Default")
      (node (ref "J2") (pin "06") (pinfunction "06_06") (pintype "passive"))
    )
    (net (code "53") (name "unconnected-(J2-Pad07)") (class "Default")
      (node (ref "J2") (pin "07") (pinfunction "07_07") (pintype "passive"))
    )
    (net (code "54") (name "unconnected-(J2-Pad09)") (class "Default")
      (node (ref "J2") (pin "09") (pinfunction "09_09") (pintype "passive"))
    )
    (net (code "55") (name "unconnected-(J2-Pad10)") (class "Default")
      (node (ref "J2") (pin "10") (pinfunction "10_10") (pintype "passive"))
    )
    (net (code "56") (name "unconnected-(J2-Pad11)") (class "Default")
      (node (ref "J2") (pin "11") (pinfunction "11_11") (pintype "passive"))
    )
    (net (code "57") (name "unconnected-(J2-Pad12)") (class "Default")
      (node (ref "J2") (pin "12") (pinfunction "12_12") (pintype "passive"))
    )
    (net (code "58") (name "unconnected-(J2-Pad13)") (class "Default")
      (node (ref "J2") (pin "13") (pinfunction "13_13") (pintype "passive"))
    )
    (net (code "59") (name "unconnected-(J2-Pad14)") (class "Default")
      (node (ref "J2") (pin "14") (pinfunction "14_14") (pintype "passive"))
    )
    (net (code "60") (name "unconnected-(J2-Pad15)") (class "Default")
      (node (ref "J2") (pin "15") (pinfunction "15_15") (pintype "passive"))
    )
    (net (code "61") (name "unconnected-(J2-Pad17)") (class "Default")
      (node (ref "J2") (pin "17") (pinfunction "17_17") (pintype "passive"))
    )
    (net (code "62") (name "unconnected-(J2-Pad18)") (class "Default")
      (node (ref "J2") (pin "18") (pinfunction "18_18") (pintype "passive"))
    )
    (net (code "63") (name "unconnected-(J3-Pad2)") (class "Default")
      (node (ref "J3") (pin "2") (pinfunction "2_2") (pintype "passive"))
    )
    (net (code "64") (name "unconnected-(J3-Pad15)") (class "Default")
      (node (ref "J3") (pin "15") (pinfunction "15_15") (pintype "passive"))
    )
  )
)
